# PM12_ATxmega128.net
KiCad netlist of a schematic drawn in Altium Designer
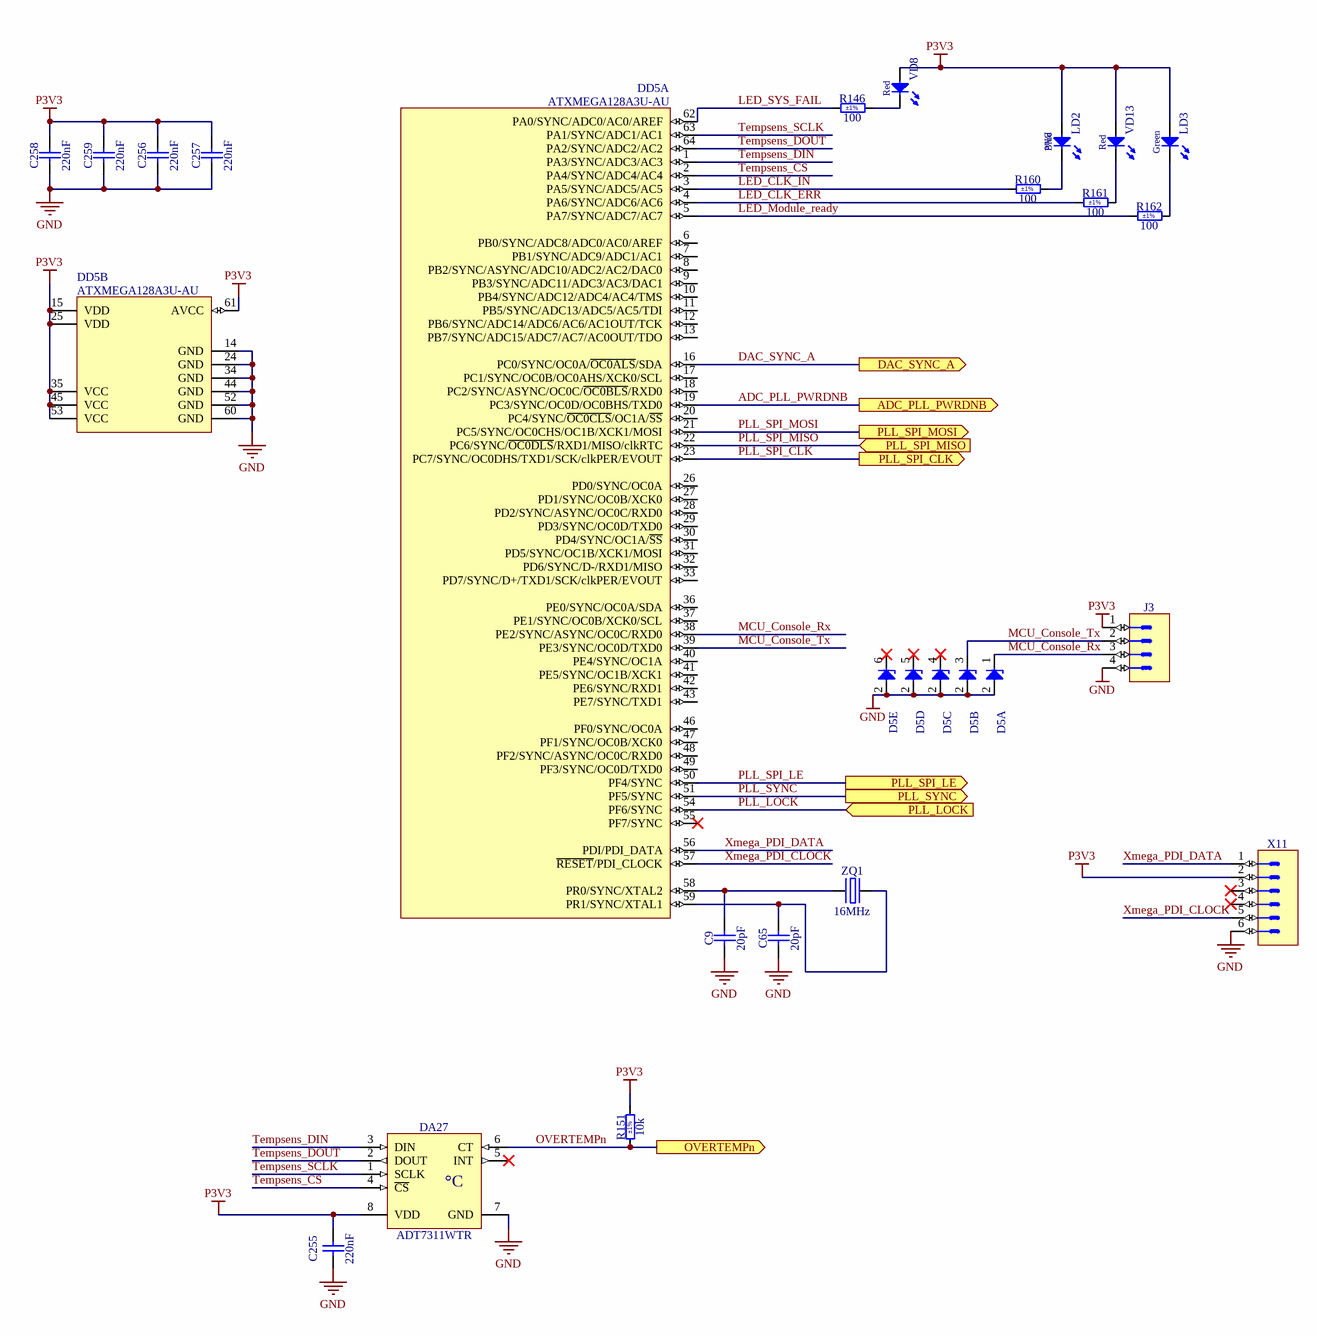
[diagram p0: PM12_ATxmega128.SchDoc]

(export (version "E")
  (design (tool "Eeschema 10.0.6"))
  (components
    (comp (ref "C9")
      (value "20pF")
      (footprint "CAPC2012X135N")
      (description "Non-polarised capacitor")
      (fields
        (field (name "PART NUMBER") "CC0805_20PF_50V_2%_C0G")
        (field (name "VOLTAGE") "50V")
        (field (name "AUTHOR") "CERN DEM HF")
      )
      (libsource (lib "Capacitors") (part "Capacitor - non polarized"))
    )
    (comp (ref "C65")
      (value "20pF")
      (footprint "CAPC2012X135N")
      (description "Non-polarised capacitor")
      (fields
        (field (name "PART NUMBER") "CC0805_20PF_50V_2%_C0G")
        (field (name "VOLTAGE") "50V")
        (field (name "AUTHOR") "CERN DEM HF")
      )
      (libsource (lib "Capacitors") (part "Capacitor - non polarized"))
    )
    (comp (ref "C255")
      (value "220nF")
      (footprint "CAPC2012X135N")
      (description "Non-polarised capacitor")
      (fields
        (field (name "PART NUMBER") "CC0805_220NF_50V_10%_X7R")
        (field (name "VOLTAGE") "50V")
        (field (name "AUTHOR") "CERN DEM JLC")
      )
      (libsource (lib "Capacitors") (part "Capacitor - non polarized"))
    )
    (comp (ref "C256")
      (value "220nF")
      (footprint "CAPC2012X135N")
      (description "Non-polarised capacitor")
      (fields
        (field (name "PART NUMBER") "CC0805_220NF_50V_10%_X7R")
        (field (name "VOLTAGE") "50V")
        (field (name "AUTHOR") "CERN DEM JLC")
      )
      (libsource (lib "Capacitors") (part "Capacitor - non polarized"))
    )
    (comp (ref "C257")
      (value "220nF")
      (footprint "CAPC2012X135N")
      (description "Non-polarised capacitor")
      (fields
        (field (name "PART NUMBER") "CC0805_220NF_50V_10%_X7R")
        (field (name "VOLTAGE") "50V")
        (field (name "AUTHOR") "CERN DEM JLC")
      )
      (libsource (lib "Capacitors") (part "Capacitor - non polarized"))
    )
    (comp (ref "C258")
      (value "220nF")
      (footprint "CAPC2012X135N")
      (description "Non-polarised capacitor")
      (fields
        (field (name "PART NUMBER") "CC0805_220NF_50V_10%_X7R")
        (field (name "VOLTAGE") "50V")
        (field (name "AUTHOR") "CERN DEM JLC")
      )
      (libsource (lib "Capacitors") (part "Capacitor - non polarized"))
    )
    (comp (ref "C259")
      (value "220nF")
      (footprint "CAPC2012X135N")
      (description "Non-polarised capacitor")
      (fields
        (field (name "PART NUMBER") "CC0805_220NF_50V_10%_X7R")
        (field (name "VOLTAGE") "50V")
        (field (name "AUTHOR") "CERN DEM JLC")
      )
      (libsource (lib "Capacitors") (part "Capacitor - non polarized"))
    )
    (comp (ref "D5")
      (value "PESD3V3L5UY")
      (footprint "SOT65P210X110-6N")
      (description "Fivefold ESD Protection Diode Arrays")
      (fields
        (field (name "VOLTAGE") "3.3V")
        (field (name "POWER") "200W")
        (field (name "AUTHOR") "CERN DEM WB")
      )
      (libsource (lib "ICs And Semiconductors") (part "PESD Array 5diodes 6pins Common anode2"))
    )
    (comp (ref "DA27")
      (value "ADT7311WTR")
      (footprint "SOIC127P600X175-8N")
      (description "±0.5°C Accurate, 16-Bit Digital SPI Temperature Sensor")
      (fields (field (name "MANUFACTURER") "ANALOG DEVICES") (field (name "AUTHOR") "CERN DEM HF"))
      (libsource (lib "ICs And Semiconductors") (part "ADT7311WTR"))
    )
    (comp (ref "DD5")
      (value "ATXMEGA128A3U-AU")
      (footprint "QFP80P1600X1600X120-64N")
      (description "8/16-bit XMEGA A3BU 32MHz Microcontroller With 256KBytes of in-System Self-Programmable Flash")
      (fields (field (name "MANUFACTURER") "MICROCHIP TECHNOLOGY") (field (name "AUTHOR") "CERN DEM HF"))
      (libsource (lib "ICs And Semiconductors") (part "ATXMEGA128A3U-AU"))
    )
    (comp (ref "J3")
      (value "Header 4")
      (footprint "SAMTEC_TSW-104-07-L-S-LL")
      (description "Connector 4 Male")
      (fields
        (field (name "PART NUMBER") "SAMTEC_TSW-104-07-L-S-LL")
        (field (name "MANUFACTURER") "SAMTEC")
        (field (name "AUTHOR") "CERN DEM MR")
      )
      (libsource (lib "Connectors") (part "Connector 4 Male"))
    )
    (comp (ref "LD2")
      (value "Blue")
      (footprint "LED_OSRAM_LB Q39G")
      (description "LED Blue 1C 2A")
      (fields
        (field (name "PART NUMBER") "LED_OSRAM_LB Q39G")
        (field (name "MANUFACTURER") "OSRAM")
        (field (name "AUTHOR") "CERN DEM HF")
      )
      (libsource (lib "ICs And Semiconductors") (part "LED Blue 1C 2A"))
    )
    (comp (ref "LD3")
      (value "Green")
      (footprint "LED_KINGBRIGHT_KPH-1608CGCK")
      (description "LED Green 1C 2A")
      (fields
        (field (name "PART NUMBER") "LED_KINGBRIGHT_KPH-1608CGCK")
        (field (name "MANUFACTURER") "KINGBRIGHT")
        (field (name "AUTHOR") "CERN DEM JLC")
      )
      (libsource (lib "ICs And Semiconductors") (part "LED Green 1C 2A"))
    )
    (comp (ref "R146")
      (value "100")
      (footprint "RESC1608X55N")
      (description "Resistor - 1%")
      (fields
        (field (name "TOLERANCE") "±1%")
        (field (name "PART NUMBER") "R0603_100R_1%_0.1W_100PPM")
        (field (name "POWER") "0.1W")
        (field (name "AUTHOR") "CERN DEM JLC")
      )
      (libsource (lib "Resistors") (part "Resistor - 1%"))
    )
    (comp (ref "R151")
      (value "10k")
      (footprint "RESC1608X55N")
      (description "Resistor - 1%")
      (fields
        (field (name "TOLERANCE") "±1%")
        (field (name "PART NUMBER") "R0603_10K_1%_0.1W_100PPM")
        (field (name "POWER") "0.1W")
        (field (name "AUTHOR") "CERN DEM JLC")
      )
      (libsource (lib "Resistors") (part "Resistor - 1%"))
    )
    (comp (ref "R160")
      (value "100")
      (footprint "RESC1608X55N")
      (description "Resistor - 1%")
      (fields
        (field (name "TOLERANCE") "±1%")
        (field (name "PART NUMBER") "R0603_100R_1%_0.1W_100PPM")
        (field (name "POWER") "0.1W")
        (field (name "AUTHOR") "CERN DEM JLC")
      )
      (libsource (lib "Resistors") (part "Resistor - 1%"))
    )
    (comp (ref "R161")
      (value "100")
      (footprint "RESC1608X55N")
      (description "Resistor - 1%")
      (fields
        (field (name "TOLERANCE") "±1%")
        (field (name "PART NUMBER") "R0603_100R_1%_0.1W_100PPM")
        (field (name "POWER") "0.1W")
        (field (name "AUTHOR") "CERN DEM JLC")
      )
      (libsource (lib "Resistors") (part "Resistor - 1%"))
    )
    (comp (ref "R162")
      (value "100")
      (footprint "RESC1608X55N")
      (description "Resistor - 1%")
      (fields
        (field (name "TOLERANCE") "±1%")
        (field (name "PART NUMBER") "R0603_100R_1%_0.1W_100PPM")
        (field (name "POWER") "0.1W")
        (field (name "AUTHOR") "CERN DEM JLC")
      )
      (libsource (lib "Resistors") (part "Resistor - 1%"))
    )
    (comp (ref "VD8")
      (value "Red")
      (footprint "LED_KINGBRIGHT_KPT-2012SURCK")
      (description "LED Red 1C 2A")
      (fields
        (field (name "PART NUMBER") "LED_KINGBRIGHT_KPT-2012SURCK")
        (field (name "MANUFACTURER") "KINGBRIGHT")
        (field (name "AUTHOR") "CERN DEM BC")
      )
      (libsource (lib "ICs And Semiconductors") (part "LED Red 1C 2A"))
    )
    (comp (ref "VD13")
      (value "Red")
      (footprint "LED_KINGBRIGHT_KPT-2012SURCK")
      (description "LED Red 1C 2A")
      (fields
        (field (name "PART NUMBER") "LED_KINGBRIGHT_KPT-2012SURCK")
        (field (name "MANUFACTURER") "KINGBRIGHT")
        (field (name "AUTHOR") "CERN DEM BC")
      )
      (libsource (lib "ICs And Semiconductors") (part "LED Red 1C 2A"))
    )
    (comp (ref "X11")
      (value "~")
      (footprint "CONNFLY_DS1013-06SSIB1-B-0")
      (description "Connector 6 Male")
      (fields
        (field (name "PART NUMBER") "CONNFLY_DS1013-06SSIB1-B-0")
        (field (name "MANUFACTURER") "CONNFLY")
        (field (name "AUTHOR") "CERN DEM HF")
      )
      (libsource (lib "Connectors") (part "Connector 6 Male"))
    )
    (comp (ref "ZQ1")
      (value "16MHz")
      (footprint "XTAL_ABRACON_ABL")
      (description "Quartz Crystal")
      (fields
        (field (name "PART NUMBER") "XTAL_16MHZ_ABRACON_ABL-16.000MHZ-B1U")
        (field (name "MANUFACTURER") "ABRACON")
        (field (name "AUTHOR") "CERN DEM HF")
      )
      (libsource (lib "ICs And Semiconductors") (part "Quartz Crystal"))
    )
  )
  (nets
    (net (code "1") (name "/ADC_PLL_PWRDNB") (class "Default")
      (node (ref "DD5") (pin "19") (pinfunction "PC3/SYNC/OC0D/OC0BHS/TXD0_19") (pintype "bidirectional"))
    )
    (net (code "2") (name "/DAC_SYNC_A") (class "Default")
      (node (ref "DD5") (pin "16") (pinfunction "PC0/SYNC/OC0A/~{OC0ALS}/SDA_16") (pintype "bidirectional"))
    )
    (net (code "3") (name "/LED_CLK_ERR") (class "Default")
      (node (ref "DD5") (pin "4") (pinfunction "PA6/SYNC/ADC6/AC6_4") (pintype "bidirectional"))
      (node (ref "R161") (pin "1") (pinfunction "1_1") (pintype "passive"))
    )
    (net (code "4") (name "/LED_CLK_IN") (class "Default")
      (node (ref "DD5") (pin "3") (pinfunction "PA5/SYNC/ADC5/AC5_3") (pintype "bidirectional"))
      (node (ref "R160") (pin "1") (pinfunction "1_1") (pintype "passive"))
    )
    (net (code "5") (name "/LED_Module_ready") (class "Default")
      (node (ref "DD5") (pin "5") (pinfunction "PA7/SYNC/ADC7/AC7_5") (pintype "bidirectional"))
      (node (ref "R162") (pin "1") (pinfunction "1_1") (pintype "passive"))
    )
    (net (code "6") (name "/LED_SYS_FAIL") (class "Default")
      (node (ref "DD5") (pin "62") (pinfunction "PA0/SYNC/ADC0/AC0/AREF_62") (pintype "bidirectional"))
      (node (ref "R146") (pin "1") (pinfunction "1_1") (pintype "passive"))
    )
    (net (code "7") (name "/MCU_Console_Rx") (class "Default")
      (node (ref "D5") (pin "1") (pinfunction "C_1") (pintype "passive"))
      (node (ref "DD5") (pin "38") (pinfunction "PE2/SYNC/ASYNC/OC0C/RXD0_38") (pintype "bidirectional"))
      (node (ref "J3") (pin "3") (pinfunction "3_3") (pintype "bidirectional"))
    )
    (net (code "8") (name "/MCU_Console_Tx") (class "Default")
      (node (ref "D5") (pin "3") (pinfunction "C_3") (pintype "passive"))
      (node (ref "DD5") (pin "39") (pinfunction "PE3/SYNC/OC0D/TXD0_39") (pintype "bidirectional"))
      (node (ref "J3") (pin "2") (pinfunction "2_2") (pintype "bidirectional"))
    )
    (net (code "9") (name "/OVERTEMPn") (class "Default")
      (node (ref "DA27") (pin "6") (pinfunction "CT_6") (pintype "input"))
      (node (ref "R151") (pin "1") (pinfunction "1_1") (pintype "passive"))
    )
    (net (code "10") (name "/PLL_LOCK") (class "Default")
      (node (ref "DD5") (pin "54") (pinfunction "PF6/SYNC_54") (pintype "bidirectional"))
    )
    (net (code "11") (name "/PLL_SPI_CLK") (class "Default")
      (node (ref "DD5") (pin "23") (pinfunction "PC7/SYNC/OC0DHS/TXD1/SCK/clkPER/EVOUT_23") (pintype "bidirectional"))
    )
    (net (code "12") (name "/PLL_SPI_LE") (class "Default")
      (node (ref "DD5") (pin "50") (pinfunction "PF4/SYNC_50") (pintype "bidirectional"))
    )
    (net (code "13") (name "/PLL_SPI_MISO") (class "Default")
      (node (ref "DD5") (pin "22") (pinfunction "PC6/SYNC/~{OC0DLS}/RXD1/MISO/clkRTC_22") (pintype "bidirectional"))
    )
    (net (code "14") (name "/PLL_SPI_MOSI") (class "Default")
      (node (ref "DD5") (pin "21") (pinfunction "PC5/SYNC/OC0CHS/OC1B/XCK1/MOSI_21") (pintype "bidirectional"))
    )
    (net (code "15") (name "/PLL_SYNC") (class "Default")
      (node (ref "DD5") (pin "51") (pinfunction "PF5/SYNC_51") (pintype "bidirectional"))
    )
    (net (code "16") (name "/Tempsens_CS") (class "Default")
      (node (ref "DA27") (pin "4") (pinfunction "~{CS}_4") (pintype "input"))
      (node (ref "DD5") (pin "2") (pinfunction "PA4/SYNC/ADC4/AC4_2") (pintype "bidirectional"))
    )
    (net (code "17") (name "/Tempsens_DIN") (class "Default")
      (node (ref "DA27") (pin "3") (pinfunction "DIN_3") (pintype "input"))
      (node (ref "DD5") (pin "1") (pinfunction "PA3/SYNC/ADC3/AC3_1") (pintype "bidirectional"))
    )
    (net (code "18") (name "/Tempsens_DOUT") (class "Default")
      (node (ref "DA27") (pin "2") (pinfunction "DOUT_2") (pintype "output"))
      (node (ref "DD5") (pin "64") (pinfunction "PA2/SYNC/ADC2/AC2_64") (pintype "bidirectional"))
    )
    (net (code "19") (name "/Tempsens_SCLK") (class "Default")
      (node (ref "DA27") (pin "1") (pinfunction "SCLK_1") (pintype "input"))
      (node (ref "DD5") (pin "63") (pinfunction "PA1/SYNC/ADC1/AC1_63") (pintype "bidirectional"))
    )
    (net (code "20") (name "/Xmega_PDI_CLOCK") (class "Default")
      (node (ref "DD5") (pin "57") (pinfunction "~{RESET}/PDI_CLOCK_57") (pintype "bidirectional"))
      (node (ref "X11") (pin "5") (pinfunction "5_5") (pintype "bidirectional"))
    )
    (net (code "21") (name "/Xmega_PDI_DATA") (class "Default")
      (node (ref "DD5") (pin "56") (pinfunction "PDI/PDI_DATA_56") (pintype "bidirectional"))
      (node (ref "X11") (pin "1") (pinfunction "1_1") (pintype "bidirectional"))
    )
    (net (code "22") (name "GND") (class "Default")
      (node (ref "C255") (pin "1") (pinfunction "1_1") (pintype "passive"))
      (node (ref "C256") (pin "1") (pinfunction "1_1") (pintype "passive"))
      (node (ref "C257") (pin "1") (pinfunction "1_1") (pintype "passive"))
      (node (ref "C258") (pin "1") (pinfunction "1_1") (pintype "passive"))
      (node (ref "C259") (pin "1") (pinfunction "1_1") (pintype "passive"))
      (node (ref "C65") (pin "1") (pinfunction "1_1") (pintype "passive"))
      (node (ref "C9") (pin "1") (pinfunction "1_1") (pintype "passive"))
      (node (ref "D5") (pin "2") (pinfunction "A_2") (pintype "passive"))
      (node (ref "DA27") (pin "7") (pinfunction "GND_7") (pintype "power_in"))
      (node (ref "DD5") (pin "14") (pinfunction "GND_14") (pintype "power_in"))
      (node (ref "DD5") (pin "24") (pinfunction "GND_24") (pintype "power_in"))
      (node (ref "DD5") (pin "34") (pinfunction "GND_34") (pintype "power_in"))
      (node (ref "DD5") (pin "44") (pinfunction "GND_44") (pintype "power_in"))
      (node (ref "DD5") (pin "52") (pinfunction "GND_52") (pintype "power_in"))
      (node (ref "DD5") (pin "60") (pinfunction "GND_60") (pintype "power_in"))
      (node (ref "J3") (pin "4") (pinfunction "4_4") (pintype "bidirectional"))
      (node (ref "X11") (pin "6") (pinfunction "6_6") (pintype "bidirectional"))
    )
    (net (code "23") (name "Net-(DD5A-PR0{slash}SYNC{slash}XTAL2)") (class "Default")
      (node (ref "C9") (pin "2") (pinfunction "2_2") (pintype "passive"))
      (node (ref "DD5") (pin "58") (pinfunction "PR0/SYNC/XTAL2_58") (pintype "bidirectional"))
      (node (ref "ZQ1") (pin "1") (pinfunction "OSC1_1") (pintype "passive"))
    )
    (net (code "24") (name "Net-(DD5A-PR1{slash}SYNC{slash}XTAL1)") (class "Default")
      (node (ref "C65") (pin "2") (pinfunction "2_2") (pintype "passive"))
      (node (ref "DD5") (pin "59") (pinfunction "PR1/SYNC/XTAL1_59") (pintype "bidirectional"))
      (node (ref "ZQ1") (pin "2") (pinfunction "OSC2_2") (pintype "passive"))
    )
    (net (code "25") (name "Net-(LD2-C)") (class "Default")
      (node (ref "LD2") (pin "1") (pinfunction "C_1") (pintype "passive"))
      (node (ref "R160") (pin "2") (pinfunction "2_2") (pintype "passive"))
    )
    (net (code "26") (name "Net-(LD3-C)") (class "Default")
      (node (ref "LD3") (pin "1") (pinfunction "C_1") (pintype "passive"))
      (node (ref "R162") (pin "2") (pinfunction "2_2") (pintype "passive"))
    )
    (net (code "27") (name "Net-(VD8-C)") (class "Default")
      (node (ref "R146") (pin "2") (pinfunction "2_2") (pintype "passive"))
      (node (ref "VD8") (pin "1") (pinfunction "C_1") (pintype "passive"))
    )
    (net (code "28") (name "Net-(VD13-C)") (class "Default")
      (node (ref "R161") (pin "2") (pinfunction "2_2") (pintype "passive"))
      (node (ref "VD13") (pin "1") (pinfunction "C_1") (pintype "passive"))
    )
    (net (code "29") (name "P3V3") (class "Default")
      (node (ref "C255") (pin "2") (pinfunction "2_2") (pintype "passive"))
      (node (ref "C256") (pin "2") (pinfunction "2_2") (pintype "passive"))
      (node (ref "C257") (pin "2") (pinfunction "2_2") (pintype "passive"))
      (node (ref "C258") (pin "2") (pinfunction "2_2") (pintype "passive"))
      (node (ref "C259") (pin "2") (pinfunction "2_2") (pintype "passive"))
      (node (ref "DA27") (pin "8") (pinfunction "VDD_8") (pintype "power_in"))
      (node (ref "DD5") (pin "15") (pinfunction "VDD_15") (pintype "power_in"))
      (node (ref "DD5") (pin "25") (pinfunction "VDD_25") (pintype "power_in"))
      (node (ref "DD5") (pin "35") (pinfunction "VCC_35") (pintype "power_in"))
      (node (ref "DD5") (pin "45") (pinfunction "VCC_45") (pintype "power_in"))
      (node (ref "DD5") (pin "53") (pinfunction "VCC_53") (pintype "power_in"))
      (node (ref "DD5") (pin "61") (pinfunction "AVCC_61") (pintype "bidirectional"))
      (node (ref "J3") (pin "1") (pinfunction "1_1") (pintype "bidirectional"))
      (node (ref "LD2") (pin "2") (pinfunction "A_2") (pintype "passive"))
      (node (ref "LD3") (pin "2") (pinfunction "A_2") (pintype "passive"))
      (node (ref "R151") (pin "2") (pinfunction "2_2") (pintype "passive"))
      (node (ref "VD13") (pin "2") (pinfunction "A_2") (pintype "passive"))
      (node (ref "VD8") (pin "2") (pinfunction "A_2") (pintype "passive"))
      (node (ref "X11") (pin "2") (pinfunction "2_2") (pintype "bidirectional"))
    )
    (net (code "30") (name "unconnected-(D5C-C-Pad4)") (class "Default")
      (node (ref "D5") (pin "4") (pinfunction "C_4") (pintype "passive+no_connect"))
    )
    (net (code "31") (name "unconnected-(D5D-C-Pad5)") (class "Default")
      (node (ref "D5") (pin "5") (pinfunction "C_5") (pintype "passive+no_connect"))
    )
    (net (code "32") (name "unconnected-(D5E-C-Pad6)") (class "Default")
      (node (ref "D5") (pin "6") (pinfunction "C_6") (pintype "passive+no_connect"))
    )
    (net (code "33") (name "unconnected-(DA27-INT-Pad5)") (class "Default")
      (node (ref "DA27") (pin "5") (pinfunction "INT_5") (pintype "output+no_connect"))
    )
    (net (code "34") (name "unconnected-(DD5A-PB0{slash}SYNC{slash}ADC8{slash}ADC0{slash}AC0{slash}AREF-Pad6)") (class "Default")
      (node (ref "DD5") (pin "6") (pinfunction "PB0/SYNC/ADC8/ADC0/AC0/AREF_6") (pintype "bidirectional"))
    )
    (net (code "35") (name "unconnected-(DD5A-PB1{slash}SYNC{slash}ADC9{slash}ADC1{slash}AC1-Pad7)") (class "Default")
      (node (ref "DD5") (pin "7") (pinfunction "PB1/SYNC/ADC9/ADC1/AC1_7") (pintype "bidirectional"))
    )
    (net (code "36") (name "unconnected-(DD5A-PB2{slash}SYNC{slash}ASYNC{slash}ADC10{slash}ADC2{slash}AC2{slash}DAC0-Pad8)") (class "Default")
      (node (ref "DD5") (pin "8") (pinfunction "PB2/SYNC/ASYNC/ADC10/ADC2/AC2/DAC0_8") (pintype "bidirectional"))
    )
    (net (code "37") (name "unconnected-(DD5A-PB3{slash}SYNC{slash}ADC11{slash}ADC3{slash}AC3{slash}DAC1-Pad9)") (class "Default")
      (node (ref "DD5") (pin "9") (pinfunction "PB3/SYNC/ADC11/ADC3/AC3/DAC1_9") (pintype "bidirectional"))
    )
    (net (code "38") (name "unconnected-(DD5A-PB4{slash}SYNC{slash}ADC12{slash}ADC4{slash}AC4{slash}TMS-Pad10)") (class "Default")
      (node (ref "DD5") (pin "10") (pinfunction "PB4/SYNC/ADC12/ADC4/AC4/TMS_10") (pintype "bidirectional"))
    )
    (net (code "39") (name "unconnected-(DD5A-PB5{slash}SYNC{slash}ADC13{slash}ADC5{slash}AC5{slash}TDI-Pad11)") (class "Default")
      (node (ref "DD5") (pin "11") (pinfunction "PB5/SYNC/ADC13/ADC5/AC5/TDI_11") (pintype "bidirectional"))
    )
    (net (code "40") (name "unconnected-(DD5A-PB6{slash}SYNC{slash}ADC14{slash}ADC6{slash}AC6{slash}AC1OUT{slash}TCK-Pad12)") (class "Default")
      (node (ref "DD5") (pin "12") (pinfunction "PB6/SYNC/ADC14/ADC6/AC6/AC1OUT/TCK_12") (pintype "bidirectional"))
    )
    (net (code "41") (name "unconnected-(DD5A-PB7{slash}SYNC{slash}ADC15{slash}ADC7{slash}AC7{slash}AC0OUT{slash}TDO-Pad13)") (class "Default")
      (node (ref "DD5") (pin "13") (pinfunction "PB7/SYNC/ADC15/ADC7/AC7/AC0OUT/TDO_13") (pintype "bidirectional"))
    )
    (net (code "42") (name "unconnected-(DD5A-PC1{slash}SYNC{slash}OC0B{slash}OC0AHS{slash}XCK0{slash}SCL-Pad17)") (class "Default")
      (node (ref "DD5") (pin "17") (pinfunction "PC1/SYNC/OC0B/OC0AHS/XCK0/SCL_17") (pintype "bidirectional"))
    )
    (net (code "43") (name "unconnected-(DD5A-PC2{slash}SYNC{slash}ASYNC{slash}OC0C{slash}~{OC0BLS}{slash}RXD0-Pad18)") (class "Default")
      (node (ref "DD5") (pin "18") (pinfunction "PC2/SYNC/ASYNC/OC0C/~{OC0BLS}/RXD0_18") (pintype "bidirectional"))
    )
    (net (code "44") (name "unconnected-(DD5A-PC4{slash}SYNC{slash}~{OC0CLS}{slash}OC1A{slash}~{SS}-Pad20)") (class "Default")
      (node (ref "DD5") (pin "20") (pinfunction "PC4/SYNC/~{OC0CLS}/OC1A/~{SS}_20") (pintype "bidirectional"))
    )
    (net (code "45") (name "unconnected-(DD5A-PD0{slash}SYNC{slash}OC0A-Pad26)") (class "Default")
      (node (ref "DD5") (pin "26") (pinfunction "PD0/SYNC/OC0A_26") (pintype "bidirectional"))
    )
    (net (code "46") (name "unconnected-(DD5A-PD1{slash}SYNC{slash}OC0B{slash}XCK0-Pad27)") (class "Default")
      (node (ref "DD5") (pin "27") (pinfunction "PD1/SYNC/OC0B/XCK0_27") (pintype "bidirectional"))
    )
    (net (code "47") (name "unconnected-(DD5A-PD2{slash}SYNC{slash}ASYNC{slash}OC0C{slash}RXD0-Pad28)") (class "Default")
      (node (ref "DD5") (pin "28") (pinfunction "PD2/SYNC/ASYNC/OC0C/RXD0_28") (pintype "bidirectional"))
    )
    (net (code "48") (name "unconnected-(DD5A-PD3{slash}SYNC{slash}OC0D{slash}TXD0-Pad29)") (class "Default")
      (node (ref "DD5") (pin "29") (pinfunction "PD3/SYNC/OC0D/TXD0_29") (pintype "bidirectional"))
    )
    (net (code "49") (name "unconnected-(DD5A-PD4{slash}SYNC{slash}OC1A{slash}~{SS}-Pad30)") (class "Default")
      (node (ref "DD5") (pin "30") (pinfunction "PD4/SYNC/OC1A/~{SS}_30") (pintype "bidirectional"))
    )
    (net (code "50") (name "unconnected-(DD5A-PD5{slash}SYNC{slash}OC1B{slash}XCK1{slash}MOSI-Pad31)") (class "Default")
      (node (ref "DD5") (pin "31") (pinfunction "PD5/SYNC/OC1B/XCK1/MOSI_31") (pintype "bidirectional"))
    )
    (net (code "51") (name "unconnected-(DD5A-PD6{slash}SYNC{slash}D-{slash}RXD1{slash}MISO-Pad32)") (class "Default")
      (node (ref "DD5") (pin "32") (pinfunction "PD6/SYNC/D-/RXD1/MISO_32") (pintype "bidirectional"))
    )
    (net (code "52") (name "unconnected-(DD5A-PD7{slash}SYNC{slash}D+{slash}TXD1{slash}SCK{slash}clkPER{slash}EVOUT-Pad33)") (class "Default")
      (node (ref "DD5") (pin "33") (pinfunction "PD7/SYNC/D+/TXD1/SCK/clkPER/EVOUT_33") (pintype "bidirectional"))
    )
    (net (code "53") (name "unconnected-(DD5A-PE0{slash}SYNC{slash}OC0A{slash}SDA-Pad36)") (class "Default")
      (node (ref "DD5") (pin "36") (pinfunction "PE0/SYNC/OC0A/SDA_36") (pintype "bidirectional"))
    )
    (net (code "54") (name "unconnected-(DD5A-PE1{slash}SYNC{slash}OC0B{slash}XCK0{slash}SCL-Pad37)") (class "Default")
      (node (ref "DD5") (pin "37") (pinfunction "PE1/SYNC/OC0B/XCK0/SCL_37") (pintype "bidirectional"))
    )
    (net (code "55") (name "unconnected-(DD5A-PE4{slash}SYNC{slash}OC1A-Pad40)") (class "Default")
      (node (ref "DD5") (pin "40") (pinfunction "PE4/SYNC/OC1A_40") (pintype "bidirectional"))
    )
    (net (code "56") (name "unconnected-(DD5A-PE5{slash}SYNC{slash}OC1B{slash}XCK1-Pad41)") (class "Default")
      (node (ref "DD5") (pin "41") (pinfunction "PE5/SYNC/OC1B/XCK1_41") (pintype "bidirectional"))
    )
    (net (code "57") (name "unconnected-(DD5A-PE6{slash}SYNC{slash}RXD1-Pad42)") (class "Default")
      (node (ref "DD5") (pin "42") (pinfunction "PE6/SYNC/RXD1_42") (pintype "bidirectional"))
    )
    (net (code "58") (name "unconnected-(DD5A-PE7{slash}SYNC{slash}TXD1-Pad43)") (class "Default")
      (node (ref "DD5") (pin "43") (pinfunction "PE7/SYNC/TXD1_43") (pintype "bidirectional"))
    )
    (net (code "59") (name "unconnected-(DD5A-PF0{slash}SYNC{slash}OC0A-Pad46)") (class "Default")
      (node (ref "DD5") (pin "46") (pinfunction "PF0/SYNC/OC0A_46") (pintype "bidirectional"))
    )
    (net (code "60") (name "unconnected-(DD5A-PF1{slash}SYNC{slash}OC0B{slash}XCK0-Pad47)") (class "Default")
      (node (ref "DD5") (pin "47") (pinfunction "PF1/SYNC/OC0B/XCK0_47") (pintype "bidirectional"))
    )
    (net (code "61") (name "unconnected-(DD5A-PF2{slash}SYNC{slash}ASYNC{slash}OC0C{slash}RXD0-Pad48)") (class "Default")
      (node (ref "DD5") (pin "48") (pinfunction "PF2/SYNC/ASYNC/OC0C/RXD0_48") (pintype "bidirectional"))
    )
    (net (code "62") (name "unconnected-(DD5A-PF3{slash}SYNC{slash}OC0D{slash}TXD0-Pad49)") (class "Default")
      (node (ref "DD5") (pin "49") (pinfunction "PF3/SYNC/OC0D/TXD0_49") (pintype "bidirectional"))
    )
    (net (code "63") (name "unconnected-(DD5A-PF7{slash}SYNC-Pad55)") (class "Default")
      (node (ref "DD5") (pin "55") (pinfunction "PF7/SYNC_55") (pintype "bidirectional+no_connect"))
    )
    (net (code "64") (name "unconnected-(X11-Pad3)") (class "Default")
      (node (ref "X11") (pin "3") (pinfunction "3_3") (pintype "bidirectional+no_connect"))
    )
    (net (code "65") (name "unconnected-(X11-Pad4)") (class "Default")
      (node (ref "X11") (pin "4") (pinfunction "4_4") (pintype "bidirectional+no_connect"))
    )
  )
)
